# Stingray.net
KiCad netlist of a schematic drawn in EAGLE
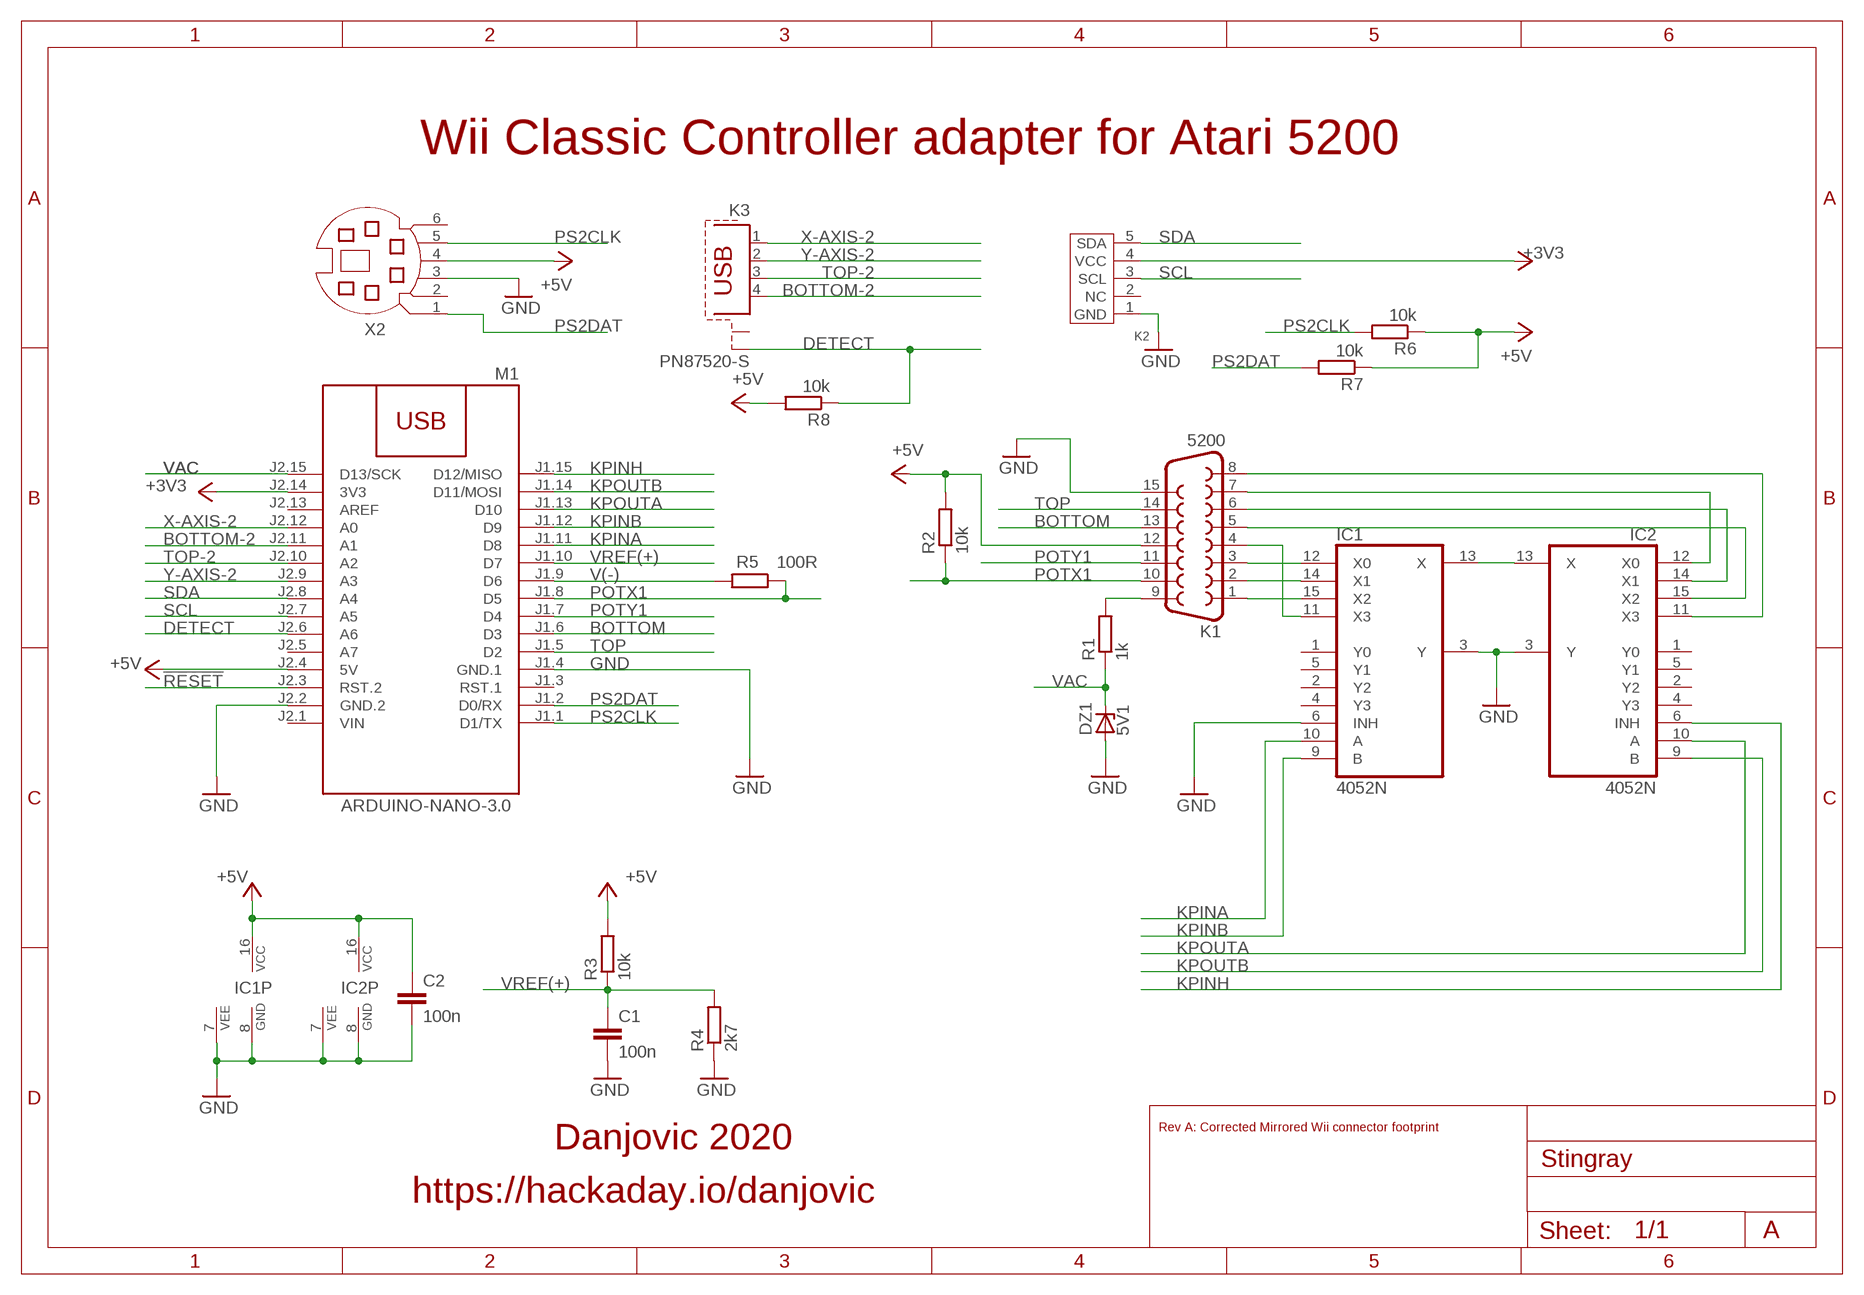
[diagram p0: schematic, sheet 1]

(export (version "E")
  (design (tool "Eeschema 10.0.6"))
  (components
    (comp (ref "C1")
      (value "100n")
      (footprint "eagle-import:C050-024X044")
      (libsource (lib "eagle-import") (part "C-EU050-024X044"))
    )
    (comp (ref "C2")
      (value "100n")
      (footprint "eagle-import:C050-024X044")
      (libsource (lib "eagle-import") (part "C-EU050-024X044"))
    )
    (comp (ref "DZ1")
      (value "5V1")
      (footprint "eagle-import:ZDIO-7.5")
      (libsource (lib "eagle-import") (part "ZENER-DIODEZD-7.5"))
    )
    (comp (ref "IC1")
      (value "4052N")
      (footprint "eagle-import:DIL16")
      (libsource (lib "eagle-import") (part "4052N"))
    )
    (comp (ref "IC2")
      (value "4052N")
      (footprint "eagle-import:DIL16")
      (libsource (lib "eagle-import") (part "4052N"))
    )
    (comp (ref "K1")
      (value "5200")
      (footprint "eagle-import:F15D")
      (libsource (lib "eagle-import") (part "F15D"))
    )
    (comp (ref "K2")
      (value "WIICHUCK")
      (footprint "eagle-import:WIICHUCK")
      (libsource (lib "eagle-import") (part "WIICHUCK"))
    )
    (comp (ref "K3")
      (value "PN87520-S")
      (footprint "eagle-import:PN87520-S")
      (libsource (lib "eagle-import") (part "PN87520-S"))
    )
    (comp (ref "M1")
      (value "ARDUINO-NANO-3.0")
      (footprint "eagle-import:ARDUINO-NANO-3.0")
      (libsource (lib "eagle-import") (part "ARDUINO-NANO-3.0"))
    )
    (comp (ref "R1")
      (value "1k")
      (footprint "eagle-import:0204_7")
      (libsource (lib "eagle-import") (part "R-EU_0204/7"))
    )
    (comp (ref "R2")
      (value "10k")
      (footprint "eagle-import:0204_7")
      (libsource (lib "eagle-import") (part "R-EU_0204/7"))
    )
    (comp (ref "R3")
      (value "10k")
      (footprint "eagle-import:0204_7")
      (libsource (lib "eagle-import") (part "R-EU_0204/7"))
    )
    (comp (ref "R4")
      (value "2k7")
      (footprint "eagle-import:0204_7")
      (libsource (lib "eagle-import") (part "R-EU_0204/7"))
    )
    (comp (ref "R5")
      (value "100R")
      (footprint "eagle-import:0204_7")
      (libsource (lib "eagle-import") (part "R-EU_0204/7"))
    )
    (comp (ref "R6")
      (value "10k")
      (footprint "eagle-import:0204_7")
      (libsource (lib "eagle-import") (part "R-EU_0204/7"))
    )
    (comp (ref "R7")
      (value "10k")
      (footprint "eagle-import:0204_7")
      (libsource (lib "eagle-import") (part "R-EU_0204/7"))
    )
    (comp (ref "R8")
      (value "10k")
      (footprint "eagle-import:0204_7")
      (libsource (lib "eagle-import") (part "R-EU_0204/7"))
    )
    (comp (ref "X2")
      (value "MD06SS")
      (footprint "eagle-import:MDIN06SS")
      (libsource (lib "eagle-import") (part "MD06SS"))
    )
  )
  (nets
    (net (code "1") (name "+3V3") (class "Default")
      (node (ref "K2") (pin "4") (pinfunction "VCC_4") (pintype "bidirectional"))
      (node (ref "M1") (pin "J2.14") (pinfunction "3V3_J2.14") (pintype "power_in"))
    )
    (net (code "2") (name "+5V") (class "Default")
      (node (ref "C2") (pin "1") (pinfunction "1_1") (pintype "passive"))
      (node (ref "IC1") (pin "16") (pinfunction "VCC_16") (pintype "power_in"))
      (node (ref "IC2") (pin "16") (pinfunction "VCC_16") (pintype "power_in"))
      (node (ref "K1") (pin "12") (pinfunction "12_12") (pintype "passive"))
      (node (ref "M1") (pin "J2.4") (pinfunction "5V_J2.4") (pintype "power_in"))
      (node (ref "R2") (pin "2") (pinfunction "2_2") (pintype "passive"))
      (node (ref "R3") (pin "2") (pinfunction "2_2") (pintype "passive"))
      (node (ref "R6") (pin "1") (pinfunction "1_1") (pintype "passive"))
      (node (ref "R7") (pin "1") (pinfunction "1_1") (pintype "passive"))
      (node (ref "R8") (pin "2") (pinfunction "2_2") (pintype "passive"))
      (node (ref "X2") (pin "4") (pinfunction "4_4") (pintype "passive"))
    )
    (net (code "3") (name "/BOTTOM") (class "Default")
      (node (ref "K1") (pin "13") (pinfunction "13_13") (pintype "passive"))
      (node (ref "M1") (pin "J1.6") (pinfunction "D3_J1.6") (pintype "bidirectional"))
    )
    (net (code "4") (name "/BOTTOM-2") (class "Default")
      (node (ref "K3") (pin "4") (pinfunction "4_4") (pintype "passive"))
      (node (ref "M1") (pin "J2.11") (pinfunction "A1_J2.11") (pintype "bidirectional"))
    )
    (net (code "5") (name "/DETECT") (class "Default")
      (node (ref "K3") (pin "S2") (pinfunction "S2_S2") (pintype "passive"))
      (node (ref "M1") (pin "J2.6") (pinfunction "A6_J2.6") (pintype "bidirectional"))
      (node (ref "R8") (pin "1") (pinfunction "1_1") (pintype "passive"))
    )
    (net (code "6") (name "/KPINA") (class "Default")
      (node (ref "IC1") (pin "10") (pinfunction "A_10") (pintype "input"))
      (node (ref "M1") (pin "J1.11") (pinfunction "D8_J1.11") (pintype "bidirectional"))
    )
    (net (code "7") (name "/KPINB") (class "Default")
      (node (ref "IC1") (pin "9") (pinfunction "B_9") (pintype "input"))
      (node (ref "M1") (pin "J1.12") (pinfunction "D9_J1.12") (pintype "bidirectional"))
    )
    (net (code "8") (name "/KPINH") (class "Default")
      (node (ref "IC2") (pin "6") (pinfunction "INH_6") (pintype "input"))
      (node (ref "M1") (pin "J1.15") (pinfunction "D12/MISO_J1.15") (pintype "bidirectional"))
    )
    (net (code "9") (name "/KPOUTA") (class "Default")
      (node (ref "IC2") (pin "10") (pinfunction "A_10") (pintype "input"))
      (node (ref "M1") (pin "J1.13") (pinfunction "D10_J1.13") (pintype "bidirectional"))
    )
    (net (code "10") (name "/KPOUTB") (class "Default")
      (node (ref "IC2") (pin "9") (pinfunction "B_9") (pintype "input"))
      (node (ref "M1") (pin "J1.14") (pinfunction "D11/MOSI_J1.14") (pintype "bidirectional"))
    )
    (net (code "11") (name "/POTX1") (class "Default")
      (node (ref "K1") (pin "10") (pinfunction "10_10") (pintype "passive"))
      (node (ref "M1") (pin "J1.8") (pinfunction "D5_J1.8") (pintype "bidirectional"))
      (node (ref "R2") (pin "1") (pinfunction "1_1") (pintype "passive"))
      (node (ref "R5") (pin "1") (pinfunction "1_1") (pintype "passive"))
    )
    (net (code "12") (name "/POTY1") (class "Default")
      (node (ref "K1") (pin "11") (pinfunction "11_11") (pintype "passive"))
      (node (ref "M1") (pin "J1.7") (pinfunction "D4_J1.7") (pintype "bidirectional"))
    )
    (net (code "13") (name "/PS2CLK") (class "Default")
      (node (ref "M1") (pin "J1.1") (pinfunction "D1/TX_J1.1") (pintype "bidirectional"))
      (node (ref "R6") (pin "2") (pinfunction "2_2") (pintype "passive"))
      (node (ref "X2") (pin "5") (pinfunction "5_5") (pintype "passive"))
    )
    (net (code "14") (name "/PS2DAT") (class "Default")
      (node (ref "M1") (pin "J1.2") (pinfunction "D0/RX_J1.2") (pintype "bidirectional"))
      (node (ref "R7") (pin "2") (pinfunction "2_2") (pintype "passive"))
      (node (ref "X2") (pin "1") (pinfunction "1_1") (pintype "passive"))
    )
    (net (code "15") (name "/SCL") (class "Default")
      (node (ref "K2") (pin "3") (pinfunction "SCL_3") (pintype "bidirectional"))
      (node (ref "M1") (pin "J2.7") (pinfunction "A5_J2.7") (pintype "bidirectional"))
    )
    (net (code "16") (name "/SDA") (class "Default")
      (node (ref "K2") (pin "5") (pinfunction "SDA_5") (pintype "bidirectional"))
      (node (ref "M1") (pin "J2.8") (pinfunction "A4_J2.8") (pintype "bidirectional"))
    )
    (net (code "17") (name "/TOP") (class "Default")
      (node (ref "K1") (pin "14") (pinfunction "14_14") (pintype "passive"))
      (node (ref "M1") (pin "J1.5") (pinfunction "D2_J1.5") (pintype "bidirectional"))
    )
    (net (code "18") (name "/TOP-2") (class "Default")
      (node (ref "K3") (pin "3") (pinfunction "3_3") (pintype "passive"))
      (node (ref "M1") (pin "J2.10") (pinfunction "A2_J2.10") (pintype "bidirectional"))
    )
    (net (code "19") (name "/V(-)") (class "Default")
      (node (ref "M1") (pin "J1.9") (pinfunction "D6_J1.9") (pintype "bidirectional"))
      (node (ref "R5") (pin "2") (pinfunction "2_2") (pintype "passive"))
    )
    (net (code "20") (name "/VAC") (class "Default")
      (node (ref "DZ1") (pin "C") (pinfunction "C_C") (pintype "passive"))
      (node (ref "M1") (pin "J2.15") (pinfunction "D13/SCK_J2.15") (pintype "bidirectional"))
      (node (ref "R1") (pin "1") (pinfunction "1_1") (pintype "passive"))
    )
    (net (code "21") (name "/VIN") (class "Default")
      (node (ref "M1") (pin "J2.1") (pinfunction "VIN_J2.1") (pintype "power_in"))
    )
    (net (code "22") (name "/VREF(+)") (class "Default")
      (node (ref "C1") (pin "1") (pinfunction "1_1") (pintype "passive"))
      (node (ref "M1") (pin "J1.10") (pinfunction "D7_J1.10") (pintype "bidirectional"))
      (node (ref "R3") (pin "1") (pinfunction "1_1") (pintype "passive"))
      (node (ref "R4") (pin "2") (pinfunction "2_2") (pintype "passive"))
    )
    (net (code "23") (name "/X-AXIS-2") (class "Default")
      (node (ref "K3") (pin "1") (pinfunction "1_1") (pintype "passive"))
      (node (ref "M1") (pin "J2.12") (pinfunction "A0_J2.12") (pintype "bidirectional"))
    )
    (net (code "24") (name "/Y-AXIS-2") (class "Default")
      (node (ref "K3") (pin "2") (pinfunction "2_2") (pintype "passive"))
      (node (ref "M1") (pin "J2.9") (pinfunction "A3_J2.9") (pintype "bidirectional"))
    )
    (net (code "25") (name "/~{RESET}") (class "Default")
      (node (ref "M1") (pin "J2.3") (pinfunction "RST.2_J2.3") (pintype "bidirectional"))
    )
    (net (code "26") (name "GND") (class "Default")
      (node (ref "C1") (pin "2") (pinfunction "2_2") (pintype "passive"))
      (node (ref "C2") (pin "2") (pinfunction "2_2") (pintype "passive"))
      (node (ref "DZ1") (pin "A") (pinfunction "A_A") (pintype "passive"))
      (node (ref "IC1") (pin "3") (pinfunction "Y_3") (pintype "bidirectional"))
      (node (ref "IC1") (pin "6") (pinfunction "INH_6") (pintype "input"))
      (node (ref "IC1") (pin "7") (pinfunction "VEE_7") (pintype "power_in"))
      (node (ref "IC1") (pin "8") (pinfunction "GND_8") (pintype "power_in"))
      (node (ref "IC2") (pin "3") (pinfunction "Y_3") (pintype "bidirectional"))
      (node (ref "IC2") (pin "7") (pinfunction "VEE_7") (pintype "power_in"))
      (node (ref "IC2") (pin "8") (pinfunction "GND_8") (pintype "power_in"))
      (node (ref "K1") (pin "15") (pinfunction "15_15") (pintype "passive"))
      (node (ref "K2") (pin "1") (pinfunction "GND_1") (pintype "bidirectional"))
      (node (ref "M1") (pin "J1.4") (pinfunction "GND.1_J1.4") (pintype "power_in"))
      (node (ref "M1") (pin "J2.2") (pinfunction "GND.2_J2.2") (pintype "power_in"))
      (node (ref "R4") (pin "1") (pinfunction "1_1") (pintype "passive"))
      (node (ref "X2") (pin "3") (pinfunction "3_3") (pintype "passive"))
    )
    (net (code "27") (name "Net-(IC1A-X)") (class "Default")
      (node (ref "IC1") (pin "13") (pinfunction "X_13") (pintype "bidirectional"))
      (node (ref "IC2") (pin "13") (pinfunction "X_13") (pintype "bidirectional"))
    )
    (net (code "28") (name "Net-(IC1A-X0)") (class "Default")
      (node (ref "IC1") (pin "12") (pinfunction "X0_12") (pintype "bidirectional"))
      (node (ref "K1") (pin "3") (pinfunction "3_3") (pintype "passive"))
    )
    (net (code "29") (name "Net-(IC1A-X1)") (class "Default")
      (node (ref "IC1") (pin "14") (pinfunction "X1_14") (pintype "bidirectional"))
      (node (ref "K1") (pin "2") (pinfunction "2_2") (pintype "passive"))
    )
    (net (code "30") (name "Net-(IC1A-X2)") (class "Default")
      (node (ref "IC1") (pin "15") (pinfunction "X2_15") (pintype "bidirectional"))
      (node (ref "K1") (pin "1") (pinfunction "1_1") (pintype "passive"))
    )
    (net (code "31") (name "Net-(IC1A-X3)") (class "Default")
      (node (ref "IC1") (pin "11") (pinfunction "X3_11") (pintype "bidirectional"))
      (node (ref "K1") (pin "4") (pinfunction "4_4") (pintype "passive"))
    )
    (net (code "32") (name "Net-(IC2A-X0)") (class "Default")
      (node (ref "IC2") (pin "12") (pinfunction "X0_12") (pintype "bidirectional"))
      (node (ref "K1") (pin "7") (pinfunction "7_7") (pintype "passive"))
    )
    (net (code "33") (name "Net-(IC2A-X1)") (class "Default")
      (node (ref "IC2") (pin "14") (pinfunction "X1_14") (pintype "bidirectional"))
      (node (ref "K1") (pin "6") (pinfunction "6_6") (pintype "passive"))
    )
    (net (code "34") (name "Net-(IC2A-X2)") (class "Default")
      (node (ref "IC2") (pin "15") (pinfunction "X2_15") (pintype "bidirectional"))
      (node (ref "K1") (pin "5") (pinfunction "5_5") (pintype "passive"))
    )
    (net (code "35") (name "Net-(IC2A-X3)") (class "Default")
      (node (ref "IC2") (pin "11") (pinfunction "X3_11") (pintype "bidirectional"))
      (node (ref "K1") (pin "8") (pinfunction "8_8") (pintype "passive"))
    )
    (net (code "36") (name "Net-(K1-Pad9)") (class "Default")
      (node (ref "K1") (pin "9") (pinfunction "9_9") (pintype "passive"))
      (node (ref "R1") (pin "2") (pinfunction "2_2") (pintype "passive"))
    )
    (net (code "37") (name "unconnected-(IC1A-Y0-Pad1)") (class "Default")
      (node (ref "IC1") (pin "1") (pinfunction "Y0_1") (pintype "bidirectional"))
    )
    (net (code "38") (name "unconnected-(IC1A-Y1-Pad5)") (class "Default")
      (node (ref "IC1") (pin "5") (pinfunction "Y1_5") (pintype "bidirectional"))
    )
    (net (code "39") (name "unconnected-(IC1A-Y2-Pad2)") (class "Default")
      (node (ref "IC1") (pin "2") (pinfunction "Y2_2") (pintype "bidirectional"))
    )
    (net (code "40") (name "unconnected-(IC1A-Y3-Pad4)") (class "Default")
      (node (ref "IC1") (pin "4") (pinfunction "Y3_4") (pintype "bidirectional"))
    )
    (net (code "41") (name "unconnected-(IC2A-Y0-Pad1)") (class "Default")
      (node (ref "IC2") (pin "1") (pinfunction "Y0_1") (pintype "bidirectional"))
    )
    (net (code "42") (name "unconnected-(IC2A-Y1-Pad5)") (class "Default")
      (node (ref "IC2") (pin "5") (pinfunction "Y1_5") (pintype "bidirectional"))
    )
    (net (code "43") (name "unconnected-(IC2A-Y2-Pad2)") (class "Default")
      (node (ref "IC2") (pin "2") (pinfunction "Y2_2") (pintype "bidirectional"))
    )
    (net (code "44") (name "unconnected-(IC2A-Y3-Pad4)") (class "Default")
      (node (ref "IC2") (pin "4") (pinfunction "Y3_4") (pintype "bidirectional"))
    )
    (net (code "45") (name "unconnected-(K2-NC-Pad2)") (class "Default")
      (node (ref "K2") (pin "2") (pinfunction "NC_2") (pintype "bidirectional"))
    )
    (net (code "46") (name "unconnected-(K3-PadS1)") (class "Default")
      (node (ref "K3") (pin "S1") (pinfunction "S1_S1") (pintype "passive"))
    )
    (net (code "47") (name "unconnected-(M1-A7-PadJ2.5)") (class "Default")
      (node (ref "M1") (pin "J2.5") (pinfunction "A7_J2.5") (pintype "bidirectional"))
    )
    (net (code "48") (name "unconnected-(M1-AREF-PadJ2.13)") (class "Default")
      (node (ref "M1") (pin "J2.13") (pinfunction "AREF_J2.13") (pintype "bidirectional"))
    )
    (net (code "49") (name "unconnected-(M1-RST.1-PadJ1.3)") (class "Default")
      (node (ref "M1") (pin "J1.3") (pinfunction "RST.1_J1.3") (pintype "bidirectional"))
    )
    (net (code "50") (name "unconnected-(X2-Pad2)") (class "Default")
      (node (ref "X2") (pin "2") (pinfunction "2_2") (pintype "passive"))
    )
    (net (code "51") (name "unconnected-(X2-Pad6)") (class "Default")
      (node (ref "X2") (pin "6") (pinfunction "6_6") (pintype "passive"))
    )
  )
)
